# LDO3V.net
KiCad netlist of a schematic drawn in Altium Designer
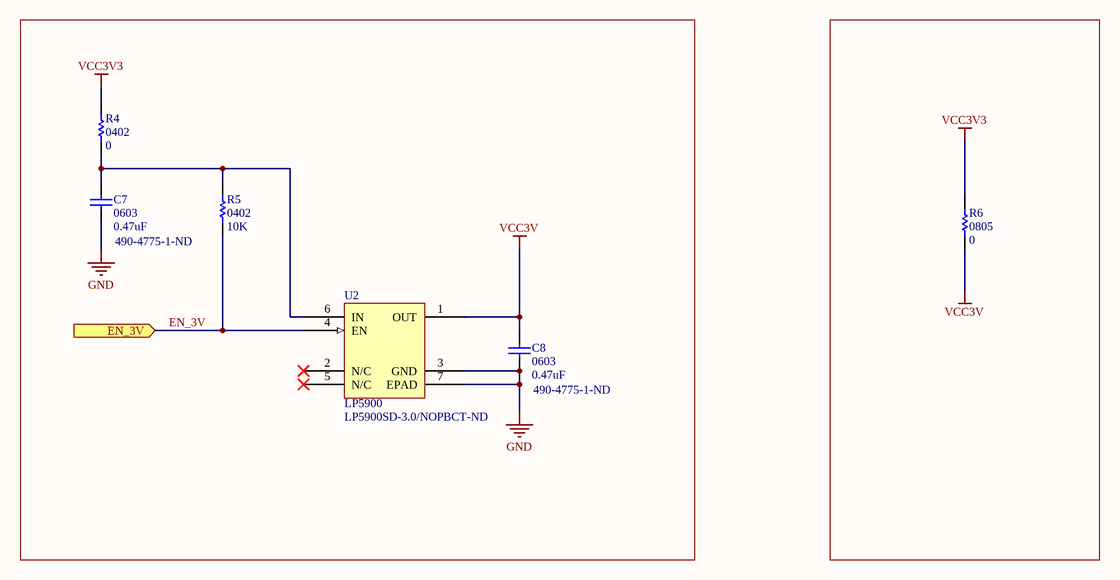
[diagram p0: LDO3V.SchDoc]

(export (version "E")
  (design (tool "Eeschema 10.0.6"))
  (components
    (comp (ref "C7")
      (value "0603")
      (footprint "RAD-0.3")
      (description "Capacitor")
      (fields
        (field (name "ALTIUM_VALUE") "0.47uF")
        (field (name "SUPPLIER PART NUMBER 1") "490-4775-1-ND")
        (field (name "MANUFACTURER") "Murata")
        (field (name "MANUFACTURER PART NUMBER") "GCM188R71C474KA55D")
        (field (name "PUBLISHER") "Altium Limited")
      )
      (libsource (lib "Miscellaneous Devices") (part "Cap"))
    )
    (comp (ref "C8")
      (value "0603")
      (footprint "RAD-0.3")
      (description "Capacitor")
      (fields
        (field (name "ALTIUM_VALUE") "0.47uF")
        (field (name "SUPPLIER PART NUMBER 1") "490-4775-1-ND")
        (field (name "MANUFACTURER") "Murata")
        (field (name "MANUFACTURER PART NUMBER") "GCM188R71C474KA55D")
        (field (name "PUBLISHER") "Altium Limited")
      )
      (libsource (lib "Miscellaneous Devices") (part "Cap"))
    )
    (comp (ref "R4")
      (value "0402")
      (footprint "AXIAL-0.3")
      (description "Resistor")
      (fields (field (name "ALTIUM_VALUE") "0") (field (name "PUBLISHER") "Altium Limited"))
      (libsource (lib "Miscellaneous Devices") (part "Res1"))
    )
    (comp (ref "R5")
      (value "0402")
      (footprint "AXIAL-0.3")
      (description "Resistor")
      (fields (field (name "ALTIUM_VALUE") "10K") (field (name "PUBLISHER") "Altium Limited"))
      (libsource (lib "Miscellaneous Devices") (part "Res1"))
    )
    (comp (ref "R6")
      (value "0805")
      (footprint "AXIAL-0.3")
      (description "Resistor")
      (fields (field (name "ALTIUM_VALUE") "0") (field (name "PUBLISHER") "Altium Limited"))
      (libsource (lib "Miscellaneous Devices") (part "Res1"))
    )
    (comp (ref "U2")
      (value "LP5900")
      (footprint "DFN220X250X80-7")
      (description "Low noise 3V low dropout regulator for analog and RF applications.")
      (fields (field (name "SUPPLIER PART NUMBER 1") "LP5900SD-3.0/NOPBCT-ND"))
      (libsource (lib "PAY") (part "LP5900"))
    )
  )
  (nets
    (net (code "1") (name "/EN_3V") (class "Default")
      (node (ref "R5") (pin "1") (pinfunction "1_1") (pintype "passive"))
      (node (ref "U2") (pin "4") (pinfunction "EN_4") (pintype "input"))
    )
    (net (code "2") (name "GND") (class "Default")
      (node (ref "C7") (pin "1") (pinfunction "1_1") (pintype "passive"))
      (node (ref "C8") (pin "1") (pinfunction "1_1") (pintype "passive"))
      (node (ref "U2") (pin "3") (pinfunction "GND_3") (pintype "power_in"))
      (node (ref "U2") (pin "7") (pinfunction "EPAD_7") (pintype "passive"))
    )
    (net (code "3") (name "Net-(U2-IN)") (class "Default")
      (node (ref "C7") (pin "2") (pinfunction "2_2") (pintype "passive"))
      (node (ref "R4") (pin "1") (pinfunction "1_1") (pintype "passive"))
      (node (ref "R5") (pin "2") (pinfunction "2_2") (pintype "passive"))
      (node (ref "U2") (pin "6") (pinfunction "IN_6") (pintype "power_in"))
    )
    (net (code "4") (name "VCC3V") (class "Default")
      (node (ref "C8") (pin "2") (pinfunction "2_2") (pintype "passive"))
      (node (ref "R6") (pin "1") (pinfunction "1_1") (pintype "passive"))
      (node (ref "U2") (pin "1") (pinfunction "OUT_1") (pintype "power_in"))
    )
    (net (code "5") (name "VCC3V3") (class "Default")
      (node (ref "R4") (pin "2") (pinfunction "2_2") (pintype "passive"))
      (node (ref "R6") (pin "2") (pinfunction "2_2") (pintype "passive"))
    )
    (net (code "6") (name "unconnected-(U2-N{slash}C-Pad2)") (class "Default")
      (node (ref "U2") (pin "2") (pinfunction "N/C_2") (pintype "passive+no_connect"))
    )
    (net (code "7") (name "unconnected-(U2-N{slash}C-Pad5)") (class "Default")
      (node (ref "U2") (pin "5") (pinfunction "N/C_5") (pintype "passive+no_connect"))
    )
  )
)
